# S7CAS-PLEIADES-CARTE-MERE_P20_Power-Tree.net
KiCad netlist of a schematic drawn in Altium Designer
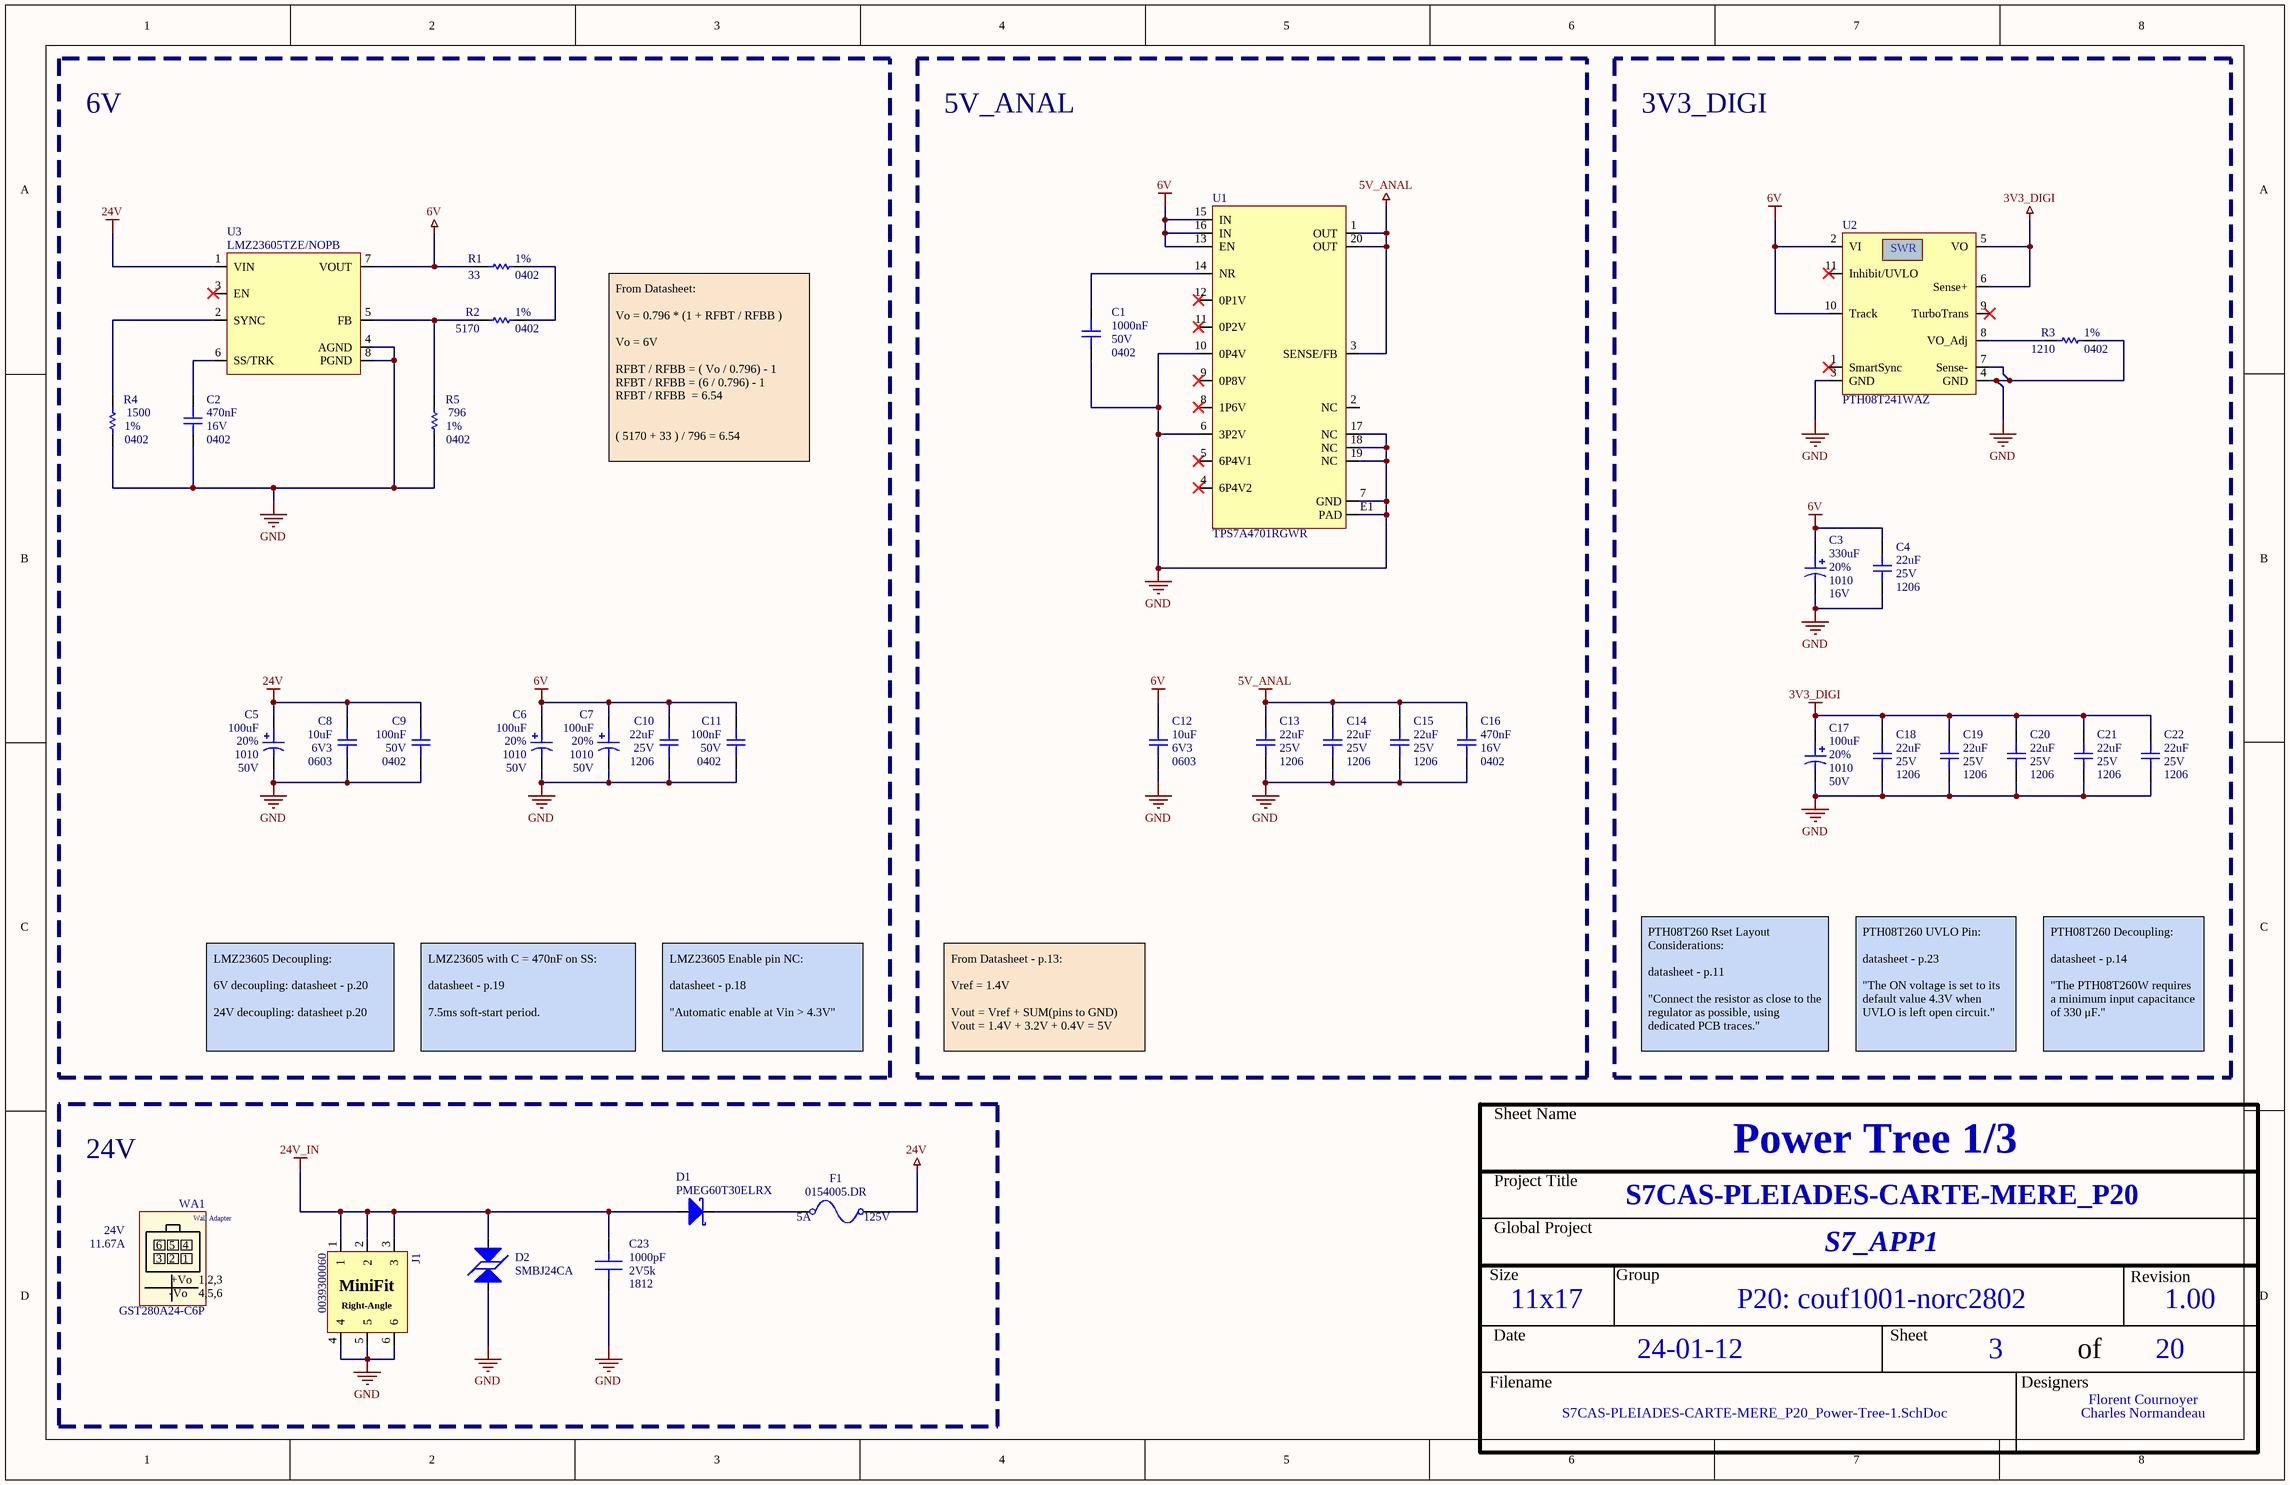
[diagram p0: S7CAS-PLEIADES-CARTE-MERE_P20_Power-Tree-1.SchDoc]

(export (version "E")
  (design (tool "Eeschema 10.0.6"))
  (components
    (comp (ref "C1")
      (value "1000nF")
      (footprint "CAP_0402")
      (description "CAP - 0402")
      (fields
        (field (name "MFG PART NUMBER") "GXT155R61E105KE01")
        (field (name "VOLTAGE") "50V")
        (field (name "PACKAGE") "0402")
        (field (name "CREATEDBY") "Jonathan Bouchard")
      )
      (libsource (lib "S7CAS_LIB2023") (part "CAP - 0402"))
    )
    (comp (ref "C2")
      (value "470nF")
      (footprint "CAP_0402")
      (description "CAP - 0402")
      (fields
        (field (name "MFG PART NUMBER") "GXT155R61C474KE01")
        (field (name "VOLTAGE") "16V")
        (field (name "PACKAGE") "0402")
        (field (name "CREATEDBY") "Jonathan Bouchard")
      )
      (libsource (lib "S7CAS_LIB2023") (part "CAP - 0402"))
    )
    (comp (ref "C3")
      (value "330uF")
      (footprint "CAP_ALU_1010_vishay")
      (description "CAP - ALU 330uF 20% 16V - 1010")
      (fields
        (field (name "MFG") "Vishay Dale")
        (field (name "MFG PART NUMBER") "MAL214699501E3")
        (field (name "VOLTAGE") "16V")
        (field (name "PACKAGE") "1010")
        (field (name "PRECISION") "20%")
        (field (name "CREATEDBY") "Jonathan Bouchard")
      )
      (libsource (lib "S7CAS_LIB2023") (part "CAP_ALU_MAL214699501E3"))
    )
    (comp (ref "C4")
      (value "22uF")
      (footprint "CAP_1206")
      (description "CAP - 1206")
      (fields
        (field (name "MFG PART NUMBER") "GRM31CC81E226KE11")
        (field (name "VOLTAGE") "25V")
        (field (name "PACKAGE") "1206")
        (field (name "CREATEDBY") "Jonathan Bouchard")
      )
      (libsource (lib "S7CAS_LIB2023") (part "CAP - 1206"))
    )
    (comp (ref "C5")
      (value "100uF")
      (footprint "CAP_ALU_1010_vishay")
      (description "CAP - ALU 100uF 20% 50V - 1010")
      (fields
        (field (name "MFG") "Vishay Dale")
        (field (name "MFG PART NUMBER") "MAL215099101E3")
        (field (name "VOLTAGE") "50V")
        (field (name "PACKAGE") "1010")
        (field (name "PRECISION") "20%")
        (field (name "CREATEDBY") "Jonathan Bouchard")
      )
      (libsource (lib "S7CAS_LIB2023") (part "CAP_ALU_MAL215099101E3"))
    )
    (comp (ref "C6")
      (value "100uF")
      (footprint "CAP_ALU_1010_vishay")
      (description "CAP - ALU 100uF 20% 50V - 1010")
      (fields
        (field (name "MFG") "Vishay Dale")
        (field (name "MFG PART NUMBER") "MAL215099101E3")
        (field (name "VOLTAGE") "50V")
        (field (name "PACKAGE") "1010")
        (field (name "PRECISION") "20%")
        (field (name "CREATEDBY") "Jonathan Bouchard")
      )
      (libsource (lib "S7CAS_LIB2023") (part "CAP_ALU_MAL215099101E3"))
    )
    (comp (ref "C7")
      (value "100uF")
      (footprint "CAP_ALU_1010_vishay")
      (description "CAP - ALU 100uF 20% 50V - 1010")
      (fields
        (field (name "MFG") "Vishay Dale")
        (field (name "MFG PART NUMBER") "MAL215099101E3")
        (field (name "VOLTAGE") "50V")
        (field (name "PACKAGE") "1010")
        (field (name "PRECISION") "20%")
        (field (name "CREATEDBY") "Jonathan Bouchard")
      )
      (libsource (lib "S7CAS_LIB2023") (part "CAP_ALU_MAL215099101E3"))
    )
    (comp (ref "C8")
      (value "10uF")
      (footprint "CAP_0603")
      (description "CAP - 0603")
      (fields
        (field (name "MFG PART NUMBER") "GRM185R60J106ME15")
        (field (name "VOLTAGE") "6V3")
        (field (name "PACKAGE") "0603")
        (field (name "CREATEDBY") "Jonathan Bouchard")
      )
      (libsource (lib "S7CAS_LIB2023") (part "CAP - 0603"))
    )
    (comp (ref "C9")
      (value "100nF")
      (footprint "CAP_0402")
      (description "CAP - 0402")
      (fields
        (field (name "MFG PART NUMBER") "GRM155R61H104KE14")
        (field (name "VOLTAGE") "50V")
        (field (name "PACKAGE") "0402")
        (field (name "CREATEDBY") "Jonathan Bouchard")
      )
      (libsource (lib "S7CAS_LIB2023") (part "CAP - 0402"))
    )
    (comp (ref "C10")
      (value "22uF")
      (footprint "CAP_1206")
      (description "CAP - 1206")
      (fields
        (field (name "MFG PART NUMBER") "GRM31CC81E226KE11")
        (field (name "VOLTAGE") "25V")
        (field (name "PACKAGE") "1206")
        (field (name "CREATEDBY") "Jonathan Bouchard")
      )
      (libsource (lib "S7CAS_LIB2023") (part "CAP - 1206"))
    )
    (comp (ref "C11")
      (value "100nF")
      (footprint "CAP_0402")
      (description "CAP - 0402")
      (fields
        (field (name "MFG PART NUMBER") "GRM155R61H104KE14")
        (field (name "VOLTAGE") "50V")
        (field (name "PACKAGE") "0402")
        (field (name "CREATEDBY") "Jonathan Bouchard")
      )
      (libsource (lib "S7CAS_LIB2023") (part "CAP - 0402"))
    )
    (comp (ref "C12")
      (value "10uF")
      (footprint "CAP_0603")
      (description "CAP - 0603")
      (fields
        (field (name "MFG PART NUMBER") "GRM185R60J106ME15")
        (field (name "VOLTAGE") "6V3")
        (field (name "PACKAGE") "0603")
        (field (name "CREATEDBY") "Jonathan Bouchard")
      )
      (libsource (lib "S7CAS_LIB2023") (part "CAP - 0603"))
    )
    (comp (ref "C13")
      (value "22uF")
      (footprint "CAP_1206")
      (description "CAP - 1206")
      (fields
        (field (name "MFG PART NUMBER") "GRM31CC81E226KE11")
        (field (name "VOLTAGE") "25V")
        (field (name "PACKAGE") "1206")
        (field (name "CREATEDBY") "Jonathan Bouchard")
      )
      (libsource (lib "S7CAS_LIB2023") (part "CAP - 1206"))
    )
    (comp (ref "C14")
      (value "22uF")
      (footprint "CAP_1206")
      (description "CAP - 1206")
      (fields
        (field (name "MFG PART NUMBER") "GRM31CC81E226KE11")
        (field (name "VOLTAGE") "25V")
        (field (name "PACKAGE") "1206")
        (field (name "CREATEDBY") "Jonathan Bouchard")
      )
      (libsource (lib "S7CAS_LIB2023") (part "CAP - 1206"))
    )
    (comp (ref "C15")
      (value "22uF")
      (footprint "CAP_1206")
      (description "CAP - 1206")
      (fields
        (field (name "MFG PART NUMBER") "GRM31CC81E226KE11")
        (field (name "VOLTAGE") "25V")
        (field (name "PACKAGE") "1206")
        (field (name "CREATEDBY") "Jonathan Bouchard")
      )
      (libsource (lib "S7CAS_LIB2023") (part "CAP - 1206"))
    )
    (comp (ref "C16")
      (value "470nF")
      (footprint "CAP_0402")
      (description "CAP - 0402")
      (fields
        (field (name "MFG PART NUMBER") "GXT155R61C474KE01")
        (field (name "VOLTAGE") "16V")
        (field (name "PACKAGE") "0402")
        (field (name "CREATEDBY") "Jonathan Bouchard")
      )
      (libsource (lib "S7CAS_LIB2023") (part "CAP - 0402"))
    )
    (comp (ref "C17")
      (value "100uF")
      (footprint "CAP_ALU_1010_vishay")
      (description "CAP - ALU 100uF 20% 50V - 1010")
      (fields
        (field (name "MFG") "Vishay Dale")
        (field (name "MFG PART NUMBER") "MAL215099101E3")
        (field (name "VOLTAGE") "50V")
        (field (name "PACKAGE") "1010")
        (field (name "PRECISION") "20%")
        (field (name "CREATEDBY") "Jonathan Bouchard")
      )
      (libsource (lib "") (part "CAP_ALU_MAL215099101E3_1"))
    )
    (comp (ref "C18")
      (value "22uF")
      (footprint "CAP_1206")
      (description "CAP - 1206")
      (fields
        (field (name "MFG PART NUMBER") "GRM31CC81E226KE11")
        (field (name "VOLTAGE") "25V")
        (field (name "PACKAGE") "1206")
        (field (name "CREATEDBY") "Jonathan Bouchard")
      )
      (libsource (lib "S7CAS_LIB2023") (part "CAP - 1206"))
    )
    (comp (ref "C19")
      (value "22uF")
      (footprint "CAP_1206")
      (description "CAP - 1206")
      (fields
        (field (name "MFG PART NUMBER") "GRM31CC81E226KE11")
        (field (name "VOLTAGE") "25V")
        (field (name "PACKAGE") "1206")
        (field (name "CREATEDBY") "Jonathan Bouchard")
      )
      (libsource (lib "S7CAS_LIB2023") (part "CAP - 1206"))
    )
    (comp (ref "C20")
      (value "22uF")
      (footprint "CAP_1206")
      (description "CAP - 1206")
      (fields
        (field (name "MFG PART NUMBER") "GRM31CC81E226KE11")
        (field (name "VOLTAGE") "25V")
        (field (name "PACKAGE") "1206")
        (field (name "CREATEDBY") "Jonathan Bouchard")
      )
      (libsource (lib "S7CAS_LIB2023") (part "CAP - 1206"))
    )
    (comp (ref "C21")
      (value "22uF")
      (footprint "CAP_1206")
      (description "CAP - 1206")
      (fields
        (field (name "MFG PART NUMBER") "GRM31CC81E226KE11")
        (field (name "VOLTAGE") "25V")
        (field (name "PACKAGE") "1206")
        (field (name "CREATEDBY") "Jonathan Bouchard")
      )
      (libsource (lib "S7CAS_LIB2023") (part "CAP - 1206"))
    )
    (comp (ref "C22")
      (value "22uF")
      (footprint "CAP_1206")
      (description "CAP - 1206")
      (fields
        (field (name "MFG PART NUMBER") "GRM31CC81E226KE11")
        (field (name "VOLTAGE") "25V")
        (field (name "PACKAGE") "1206")
        (field (name "CREATEDBY") "Jonathan Bouchard")
      )
      (libsource (lib "S7CAS_LIB2023") (part "CAP - 1206"))
    )
    (comp (ref "C23")
      (value "1000pF")
      (footprint "CAP_CER_1812")
      (description "CAP - CER 1000PF 2.5KV X7R - 1812")
      (fields
        (field (name "TOLERANCE") "10%")
        (field (name "PACKAGE") "1812")
        (field (name "VOLTAGE RATING") "2V5k")
        (field (name "Comment") "1812WC102KAT1A")
      )
      (libsource (lib "LIB_TEMP_P20_FLORENT_COURNOYER_SCH") (part "CAP_CER_1812WC102KAT1A"))
    )
    (comp (ref "D1")
      (value "PMEG60T30ELRX")
      (footprint "DIO_SCHOTTKY_PMEG60T30ELRX")
      (description "DIO -  SCHOTTKY 60V 3A - SOD-123W")
      (fields
        (field (name "CREATEDBY/DATE") "Jonathan Bouchard 2020-03-23")
        (field (name "VERIFIEDBY") "C.Paulin - 22/04/2020")
      )
      (libsource (lib "S7CAS_LIB2023") (part "DIO_SCHOTTKY_PMEG60T30ELRX"))
    )
    (comp (ref "D2")
      (value "SMBJ24CA")
      (footprint "TVS_PWR_SMBJ36CA")
      (description "TVS - 24V 26.7V 600W - DO214AA")
      (fields
        (field (name "CREATEDBY/DATE") "Arnaud Samson - 06/07/18")
        (field (name "VERIFIEDBY") "Jonathan Bouchard - 2018-07-13")
      )
      (libsource (lib "S7CAS_LIB2023") (part "TVS_PWR_SMBJ24CA"))
    )
    (comp (ref "F1")
      (value "0154005.DR")
      (footprint "FUS_0154XXX.DR")
      (description "FUS - 5 A 125 VAC/VDC - 2-SMD")
      (fields
        (field (name "VOLTAGE RATING") "125V")
        (field (name "CURRENT RATING") "5A")
        (field (name "CREATEDBY/DATE") "Arnaud Samson - 06/07/18")
        (field (name "VERIFIEDBY") "Jonathan Bouchard 2018-07-16")
      )
      (libsource (lib "S7CAS_LIB2023") (part "FUS_0154005.DR"))
    )
    (comp (ref "J1")
      (value "0039300060")
      (footprint "CON_MINIFIT_0039300060")
      (description "CON - Mini-Fit Through Hole, Right Angle 6 position")
      (fields
        (field (name "CREATEDBY/DATE") "Joel Lemay 2018-06-21")
        (field (name "VERIFIEDBY") "Caroline Paulin - 10 sept 2018")
      )
      (libsource (lib "S7CAS_LIB2023") (part "CON_MINIFIT_0039300060"))
    )
    (comp (ref "R1")
      (value "33")
      (footprint "RES_0402")
      (description "RES - 0402")
      (fields
        (field (name "VOLTAGE") "50V")
        (field (name "MFG PART NUMBER") "CRCW040233R0FKEDC")
        (field (name "PACKAGE") "0402")
        (field (name "PRECISION") "1%")
        (field (name "CREATEDBY") "Jonathan Bouchard")
      )
      (libsource (lib "S7CAS_LIB2023") (part "RES - 0402"))
    )
    (comp (ref "R2")
      (value "5170")
      (footprint "RES_0402")
      (description "RES - 0402")
      (fields
        (field (name "VOLTAGE") "50V")
        (field (name "MFG PART NUMBER") "RN73H1ETTP5171F50")
        (field (name "PACKAGE") "0402")
        (field (name "PRECISION") "1%")
        (field (name "CREATEDBY") "Jonathan Bouchard")
      )
      (libsource (lib "S7CAS_LIB2023") (part "RES - 0402"))
    )
    (comp (ref "R3")
      (value "1210")
      (footprint "RES_0402")
      (description "RES - 0402")
      (fields
        (field (name "VOLTAGE") "50V")
        (field (name "MFG PART NUMBER") "CRCW04021K21FKEDC")
        (field (name "PACKAGE") "0402")
        (field (name "PRECISION") "1%")
        (field (name "CREATEDBY") "Jonathan Bouchard")
      )
      (libsource (lib "S7CAS_LIB2023") (part "RES - 0402"))
    )
    (comp (ref "R4")
      (value "1500")
      (footprint "RES_0402")
      (description "RES - 0402")
      (fields
        (field (name "VOLTAGE") "50V")
        (field (name "POWER") "1/16W")
        (field (name "PACKAGE") "0402")
        (field (name "PRECISION") "1%")
        (field (name "CREATEDBY") "Jonathan Bouchard")
      )
      (libsource (lib "S7CAS_LIB2023") (part "RES - 0402"))
    )
    (comp (ref "R5")
      (value "796")
      (footprint "RES_0402")
      (description "RES - 0402")
      (fields
        (field (name "VOLTAGE") "50V")
        (field (name "MFG PART NUMBER") "RN73H1ETTP7960F50")
        (field (name "PACKAGE") "0402")
        (field (name "PRECISION") "1%")
        (field (name "CREATEDBY") "Jonathan Bouchard")
      )
      (libsource (lib "S7CAS_LIB2023") (part "RES - 0402"))
    )
    (comp (ref "U1")
      (value "TPS7A4701RGWR")
      (footprint "REG_TPS7A4701RGWR")
      (description "REG - LINEAR POS ADJ 1A - 20VQFN")
      (fields
        (field (name "CREATEDBY/DATE") "L-P Gauthier / 2018-05-29")
        (field (name "VERIFIEDBY") "Caroline Paulin - 28 sept 2018")
      )
      (libsource (lib "S7CAS_LIB2023") (part "REG_LDO_TPS7A4701RGWR"))
    )
    (comp (ref "U2")
      (value "PTH08T241WAZ")
      (footprint "REG_SWR_PTH08T241WAZ")
      (description "REG - MODULE PIP 10A 14VIN - 11-SMD")
      (fields
        (field (name "CREATEDBY/DATE") "Olivier Bernard / 6/5/2018")
        (field (name "VERIFIEDBY") "Caroline Paulin / 10 juillet 2018")
      )
      (libsource (lib "S7CAS_LIB2023") (part "REG_SWR_PTH08T241WAZ"))
    )
    (comp (ref "U3")
      (value "LMZ23605TZE/NOPB")
      (footprint "REG_SWR_LMZ23605TZE/NOPB")
      (description "REG - IC BUCK SYNC 36V 5A - TO-PMOD-7")
      (fields
        (field (name "CREATEDBY/DATE") "Arnaud Samson - 05/07/18")
        (field (name "VERIFIEDBY") "Jonathan Bouchard 2018-07-13")
      )
      (libsource (lib "S7CAS_LIB2023") (part "REG_SWR_LMZ23605TZE/NOPB"))
    )
    (comp (ref "WA1")
      (value "GST280A24-C6P")
      (footprint "Model Name")
      (description "UND - AC/DC DESKTOP ADAPTER 24V 280W - MEC")
      (fields
        (field (name "TOLERANCE") "±3%")
        (field (name "CURRENT RATING") "11.67A")
        (field (name "ALTIUM_VALUE") "24V")
        (field (name "CREATEDBY/DATE") "Caroline Paulin - 5 avril 2019")
        (field (name "VERIFIEDBY") "Nicolas V. (2019-07-05)")
      )
      (libsource (lib "S7CAS_LIB2023") (part "UND_GST280A24-C6P"))
    )
  )
  (nets
    (net (code "1") (name "3V3_DIGI") (class "Default")
      (node (ref "C17") (pin "1") (pinfunction "1_1") (pintype "passive"))
      (node (ref "C18") (pin "2") (pinfunction "2_2") (pintype "passive"))
      (node (ref "C19") (pin "2") (pinfunction "2_2") (pintype "passive"))
      (node (ref "C20") (pin "2") (pinfunction "2_2") (pintype "passive"))
      (node (ref "C21") (pin "2") (pinfunction "2_2") (pintype "passive"))
      (node (ref "C22") (pin "2") (pinfunction "2_2") (pintype "passive"))
      (node (ref "U2") (pin "5") (pinfunction "VO_5") (pintype "passive"))
      (node (ref "U2") (pin "6") (pinfunction "Sense+_6") (pintype "passive"))
    )
    (net (code "2") (name "5V_ANAL") (class "Default")
      (node (ref "C13") (pin "2") (pinfunction "2_2") (pintype "passive"))
      (node (ref "C14") (pin "2") (pinfunction "2_2") (pintype "passive"))
      (node (ref "C15") (pin "2") (pinfunction "2_2") (pintype "passive"))
      (node (ref "C16") (pin "2") (pinfunction "2_2") (pintype "passive"))
      (node (ref "U1") (pin "1") (pinfunction "OUT_1") (pintype "passive"))
      (node (ref "U1") (pin "20") (pinfunction "OUT_20") (pintype "passive"))
      (node (ref "U1") (pin "3") (pinfunction "SENSE/FB_3") (pintype "passive"))
    )
    (net (code "3") (name "6V") (class "Default")
      (node (ref "C10") (pin "2") (pinfunction "2_2") (pintype "passive"))
      (node (ref "C11") (pin "2") (pinfunction "2_2") (pintype "passive"))
      (node (ref "C12") (pin "2") (pinfunction "2_2") (pintype "passive"))
      (node (ref "C3") (pin "1") (pinfunction "1_1") (pintype "passive"))
      (node (ref "C4") (pin "2") (pinfunction "2_2") (pintype "passive"))
      (node (ref "C6") (pin "1") (pinfunction "1_1") (pintype "passive"))
      (node (ref "C7") (pin "1") (pinfunction "1_1") (pintype "passive"))
      (node (ref "R1") (pin "2") (pinfunction "2_2") (pintype "passive"))
      (node (ref "U1") (pin "13") (pinfunction "EN_13") (pintype "passive"))
      (node (ref "U1") (pin "15") (pinfunction "IN_15") (pintype "passive"))
      (node (ref "U1") (pin "16") (pinfunction "IN_16") (pintype "passive"))
      (node (ref "U2") (pin "10") (pinfunction "Track_10") (pintype "passive"))
      (node (ref "U2") (pin "2") (pinfunction "VI_2") (pintype "passive"))
      (node (ref "U3") (pin "7") (pinfunction "VOUT_7") (pintype "passive"))
    )
    (net (code "4") (name "24V") (class "Default")
      (node (ref "C5") (pin "1") (pinfunction "1_1") (pintype "passive"))
      (node (ref "C8") (pin "2") (pinfunction "2_2") (pintype "passive"))
      (node (ref "C9") (pin "2") (pinfunction "2_2") (pintype "passive"))
      (node (ref "F1") (pin "2") (pinfunction "2_2") (pintype "passive"))
      (node (ref "U3") (pin "1") (pinfunction "VIN_1") (pintype "passive"))
    )
    (net (code "5") (name "24V_IN") (class "Default")
      (node (ref "C23") (pin "1") (pinfunction "1_1") (pintype "passive"))
      (node (ref "D1") (pin "A") (pinfunction "A_A") (pintype "passive"))
      (node (ref "D2") (pin "1") (pinfunction "1_1") (pintype "passive"))
      (node (ref "J1") (pin "1") (pinfunction "1_1") (pintype "passive"))
      (node (ref "J1") (pin "2") (pinfunction "2_2") (pintype "passive"))
      (node (ref "J1") (pin "3") (pinfunction "3_3") (pintype "passive"))
    )
    (net (code "6") (name "GND") (class "Default")
      (node (ref "C1") (pin "2") (pinfunction "2_2") (pintype "passive"))
      (node (ref "C10") (pin "1") (pinfunction "1_1") (pintype "passive"))
      (node (ref "C11") (pin "1") (pinfunction "1_1") (pintype "passive"))
      (node (ref "C12") (pin "1") (pinfunction "1_1") (pintype "passive"))
      (node (ref "C13") (pin "1") (pinfunction "1_1") (pintype "passive"))
      (node (ref "C14") (pin "1") (pinfunction "1_1") (pintype "passive"))
      (node (ref "C15") (pin "1") (pinfunction "1_1") (pintype "passive"))
      (node (ref "C16") (pin "1") (pinfunction "1_1") (pintype "passive"))
      (node (ref "C17") (pin "2") (pinfunction "2_2") (pintype "passive"))
      (node (ref "C18") (pin "1") (pinfunction "1_1") (pintype "passive"))
      (node (ref "C19") (pin "1") (pinfunction "1_1") (pintype "passive"))
      (node (ref "C2") (pin "1") (pinfunction "1_1") (pintype "passive"))
      (node (ref "C20") (pin "1") (pinfunction "1_1") (pintype "passive"))
      (node (ref "C21") (pin "1") (pinfunction "1_1") (pintype "passive"))
      (node (ref "C22") (pin "1") (pinfunction "1_1") (pintype "passive"))
      (node (ref "C23") (pin "2") (pinfunction "2_2") (pintype "passive"))
      (node (ref "C3") (pin "2") (pinfunction "2_2") (pintype "passive"))
      (node (ref "C4") (pin "1") (pinfunction "1_1") (pintype "passive"))
      (node (ref "C5") (pin "2") (pinfunction "2_2") (pintype "passive"))
      (node (ref "C6") (pin "2") (pinfunction "2_2") (pintype "passive"))
      (node (ref "C7") (pin "2") (pinfunction "2_2") (pintype "passive"))
      (node (ref "C8") (pin "1") (pinfunction "1_1") (pintype "passive"))
      (node (ref "C9") (pin "1") (pinfunction "1_1") (pintype "passive"))
      (node (ref "D2") (pin "2") (pinfunction "2_2") (pintype "passive"))
      (node (ref "J1") (pin "4") (pinfunction "4_4") (pintype "passive"))
      (node (ref "J1") (pin "5") (pinfunction "5_5") (pintype "passive"))
      (node (ref "J1") (pin "6") (pinfunction "6_6") (pintype "passive"))
      (node (ref "R3") (pin "1") (pinfunction "1_1") (pintype "passive"))
      (node (ref "R4") (pin "1") (pinfunction "1_1") (pintype "passive"))
      (node (ref "R5") (pin "1") (pinfunction "1_1") (pintype "passive"))
      (node (ref "U1") (pin "10") (pinfunction "0P4V_10") (pintype "passive"))
      (node (ref "U1") (pin "17") (pinfunction "NC_17") (pintype "passive"))
      (node (ref "U1") (pin "18") (pinfunction "NC_18") (pintype "passive"))
      (node (ref "U1") (pin "19") (pinfunction "NC_19") (pintype "passive"))
      (node (ref "U1") (pin "6") (pinfunction "3P2V_6") (pintype "passive"))
      (node (ref "U1") (pin "7") (pinfunction "GND_7") (pintype "passive"))
      (node (ref "U1") (pin "E1") (pinfunction "PAD_E1") (pintype "passive"))
      (node (ref "U2") (pin "3") (pinfunction "GND_3") (pintype "passive"))
      (node (ref "U2") (pin "4") (pinfunction "GND_4") (pintype "passive"))
      (node (ref "U2") (pin "7") (pinfunction "Sense-_7") (pintype "passive"))
      (node (ref "U3") (pin "4") (pinfunction "AGND_4") (pintype "passive"))
      (node (ref "U3") (pin "8") (pinfunction "PGND_8") (pintype "passive"))
    )
    (net (code "7") (name "Net-(D1-PadK)") (class "Default")
      (node (ref "D1") (pin "K") (pinfunction "K_K") (pintype "passive"))
      (node (ref "F1") (pin "1") (pinfunction "1_1") (pintype "passive"))
    )
    (net (code "8") (name "Net-(R1-Pad1)") (class "Default")
      (node (ref "R1") (pin "1") (pinfunction "1_1") (pintype "passive"))
      (node (ref "R2") (pin "1") (pinfunction "1_1") (pintype "passive"))
    )
    (net (code "9") (name "Net-(U1-NR)") (class "Default")
      (node (ref "C1") (pin "1") (pinfunction "1_1") (pintype "passive"))
      (node (ref "U1") (pin "14") (pinfunction "NR_14") (pintype "passive"))
    )
    (net (code "10") (name "Net-(U2-VO_Adj)") (class "Default")
      (node (ref "R3") (pin "2") (pinfunction "2_2") (pintype "passive"))
      (node (ref "U2") (pin "8") (pinfunction "VO_Adj_8") (pintype "passive"))
    )
    (net (code "11") (name "Net-(U3-FB)") (class "Default")
      (node (ref "R2") (pin "2") (pinfunction "2_2") (pintype "passive"))
      (node (ref "R5") (pin "2") (pinfunction "2_2") (pintype "passive"))
      (node (ref "U3") (pin "5") (pinfunction "FB_5") (pintype "passive"))
    )
    (net (code "12") (name "Net-(U3-SS{slash}TRK)") (class "Default")
      (node (ref "C2") (pin "2") (pinfunction "2_2") (pintype "passive"))
      (node (ref "U3") (pin "6") (pinfunction "SS/TRK_6") (pintype "passive"))
    )
    (net (code "13") (name "Net-(U3-SYNC)") (class "Default")
      (node (ref "R4") (pin "2") (pinfunction "2_2") (pintype "passive"))
      (node (ref "U3") (pin "2") (pinfunction "SYNC_2") (pintype "passive"))
    )
    (net (code "14") (name "unconnected-(U1-0P1V-Pad12)") (class "Default")
      (node (ref "U1") (pin "12") (pinfunction "0P1V_12") (pintype "passive+no_connect"))
    )
    (net (code "15") (name "unconnected-(U1-0P2V-Pad11)") (class "Default")
      (node (ref "U1") (pin "11") (pinfunction "0P2V_11") (pintype "passive+no_connect"))
    )
    (net (code "16") (name "unconnected-(U1-0P8V-Pad9)") (class "Default")
      (node (ref "U1") (pin "9") (pinfunction "0P8V_9") (pintype "passive+no_connect"))
    )
    (net (code "17") (name "unconnected-(U1-1P6V-Pad8)") (class "Default")
      (node (ref "U1") (pin "8") (pinfunction "1P6V_8") (pintype "passive+no_connect"))
    )
    (net (code "18") (name "unconnected-(U1-6P4V1-Pad5)") (class "Default")
      (node (ref "U1") (pin "5") (pinfunction "6P4V1_5") (pintype "passive+no_connect"))
    )
    (net (code "19") (name "unconnected-(U1-6P4V2-Pad4)") (class "Default")
      (node (ref "U1") (pin "4") (pinfunction "6P4V2_4") (pintype "passive+no_connect"))
    )
    (net (code "20") (name "unconnected-(U1-NC-Pad2)") (class "Default")
      (node (ref "U1") (pin "2") (pinfunction "NC_2") (pintype "passive"))
    )
    (net (code "21") (name "unconnected-(U2-Inhibit{slash}UVLO-Pad11)") (class "Default")
      (node (ref "U2") (pin "11") (pinfunction "Inhibit/UVLO_11") (pintype "passive+no_connect"))
    )
    (net (code "22") (name "unconnected-(U2-SmartSync-Pad1)") (class "Default")
      (node (ref "U2") (pin "1") (pinfunction "SmartSync_1") (pintype "passive+no_connect"))
    )
    (net (code "23") (name "unconnected-(U2-TurboTrans-Pad9)") (class "Default")
      (node (ref "U2") (pin "9") (pinfunction "TurboTrans_9") (pintype "passive+no_connect"))
    )
    (net (code "24") (name "unconnected-(U3-EN-Pad3)") (class "Default")
      (node (ref "U3") (pin "3") (pinfunction "EN_3") (pintype "passive+no_connect"))
    )
  )
)
